# controlTP2.net
KiCad netlist of a schematic drawn in Altium Designer
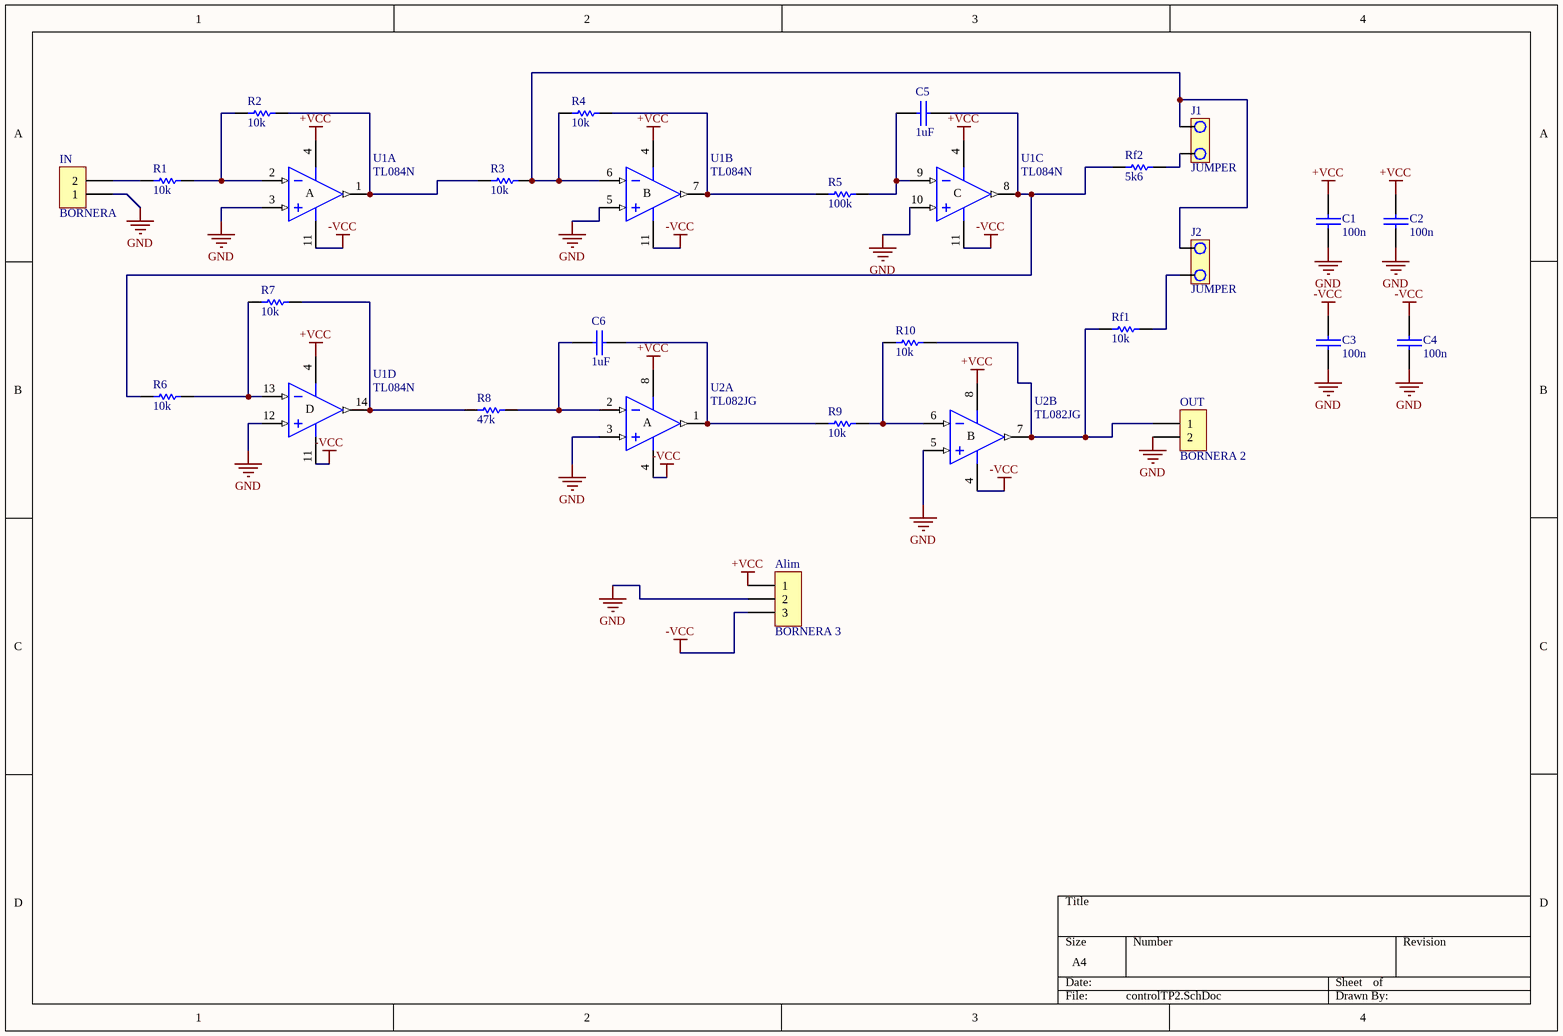
[diagram p0: controlTP2.SchDoc]

(export (version "E")
  (design (tool "Eeschema 10.0.6"))
  (components
    (comp (ref "Alim")
      (value "BORNERA 3")
      (footprint "BORNERA3")
      (libsource (lib "LIBEBAL") (part "BORNERA 3"))
    )
    (comp (ref "C1") (value "100n") (footprint "CAP200") (libsource (lib "LIBEBAL") (part "CAP")))
    (comp (ref "C2") (value "100n") (footprint "CAP200") (libsource (lib "LIBEBAL") (part "CAP")))
    (comp (ref "C3") (value "100n") (footprint "CAP200") (libsource (lib "LIBEBAL") (part "CAP")))
    (comp (ref "C4") (value "100n") (footprint "CAP200") (libsource (lib "LIBEBAL") (part "CAP")))
    (comp (ref "C5") (value "1uF") (footprint "CAP200") (libsource (lib "LIBEBAL") (part "CAP")))
    (comp (ref "C6") (value "1uF") (footprint "CAP200") (libsource (lib "LIBEBAL") (part "CAP")))
    (comp (ref "IN") (value "BORNERA") (footprint "BORNERA2") (libsource (lib "") (part "BORNERA 2_1")))
    (comp (ref "J1") (value "JUMPER") (footprint "JUMPER2") (libsource (lib "LIBEBAL") (part "JUMPER")))
    (comp (ref "J2") (value "JUMPER") (footprint "JUMPER2") (libsource (lib "LIBEBAL") (part "JUMPER")))
    (comp (ref "OUT")
      (value "BORNERA 2")
      (footprint "BORNERA2")
      (libsource (lib "LIBEBAL") (part "BORNERA 2"))
    )
    (comp (ref "R1") (value "10k") (footprint "RES400") (libsource (lib "LIBEBAL") (part "RES")))
    (comp (ref "R2") (value "10k") (footprint "RES400") (libsource (lib "LIBEBAL") (part "RES")))
    (comp (ref "R3") (value "10k") (footprint "RES400") (libsource (lib "LIBEBAL") (part "RES")))
    (comp (ref "R4") (value "10k") (footprint "RES400") (libsource (lib "LIBEBAL") (part "RES")))
    (comp (ref "R5") (value "100k") (footprint "RES400") (libsource (lib "LIBEBAL") (part "RES")))
    (comp (ref "R6") (value "10k") (footprint "RES400") (libsource (lib "LIBEBAL") (part "RES")))
    (comp (ref "R7") (value "10k") (footprint "RES400") (libsource (lib "LIBEBAL") (part "RES")))
    (comp (ref "R8") (value "47k") (footprint "RES400") (libsource (lib "LIBEBAL") (part "RES")))
    (comp (ref "R9") (value "10k") (footprint "RES400") (libsource (lib "LIBEBAL") (part "RES")))
    (comp (ref "R10") (value "10k") (footprint "RES400") (libsource (lib "LIBEBAL") (part "RES")))
    (comp (ref "Rf1") (value "10k") (footprint "RES400") (libsource (lib "LIBEBAL") (part "RES")))
    (comp (ref "Rf2") (value "5k6") (footprint "RES400") (libsource (lib "LIBEBAL") (part "RES")))
    (comp (ref "U1")
      (value "TL084N")
      (footprint "N014")
      (description "JFET-Input Operational Amplifier")
      (fields (field (name "PUBLISHER") "Altium Limited"))
      (libsource (lib "TI Operational Amplifier") (part "TL084N"))
    )
    (comp (ref "U2")
      (value "TL082JG")
      (footprint "JG008")
      (description "JFET-Input Operational Amplifier")
      (fields (field (name "PUBLISHER") "Altium Limited"))
      (libsource (lib "TI Operational Amplifier") (part "TL082JG"))
    )
  )
  (nets
    (net (code "1") (name "+VCC") (class "Default")
      (node (ref "Alim") (pin "1") (pinfunction "1_1") (pintype "passive"))
      (node (ref "C1") (pin "1") (pinfunction "1_1") (pintype "passive"))
      (node (ref "C2") (pin "1") (pinfunction "1_1") (pintype "passive"))
      (node (ref "U1") (pin "4") (pinfunction "V+_4") (pintype "power_in"))
      (node (ref "U2") (pin "8") (pinfunction "V+_8") (pintype "power_in"))
    )
    (net (code "2") (name "-VCC") (class "Default")
      (node (ref "Alim") (pin "3") (pinfunction "3_3") (pintype "passive"))
      (node (ref "C3") (pin "1") (pinfunction "1_1") (pintype "passive"))
      (node (ref "C4") (pin "1") (pinfunction "1_1") (pintype "passive"))
      (node (ref "U1") (pin "11") (pinfunction "V-_11") (pintype "power_in"))
      (node (ref "U2") (pin "4") (pinfunction "V-_4") (pintype "power_in"))
    )
    (net (code "3") (name "GND") (class "Default")
      (node (ref "Alim") (pin "2") (pinfunction "2_2") (pintype "passive"))
      (node (ref "C1") (pin "2") (pinfunction "2_2") (pintype "passive"))
      (node (ref "C2") (pin "2") (pinfunction "2_2") (pintype "passive"))
      (node (ref "C3") (pin "2") (pinfunction "2_2") (pintype "passive"))
      (node (ref "C4") (pin "2") (pinfunction "2_2") (pintype "passive"))
      (node (ref "IN") (pin "1") (pinfunction "1_1") (pintype "passive"))
      (node (ref "OUT") (pin "2") (pinfunction "2_2") (pintype "passive"))
      (node (ref "U1") (pin "10") (pinfunction "IN+_10") (pintype "input"))
      (node (ref "U1") (pin "12") (pinfunction "IN+_12") (pintype "input"))
      (node (ref "U1") (pin "3") (pinfunction "IN+_3") (pintype "input"))
      (node (ref "U1") (pin "5") (pinfunction "IN+_5") (pintype "input"))
      (node (ref "U2") (pin "3") (pinfunction "IN+_3") (pintype "input"))
      (node (ref "U2") (pin "5") (pinfunction "IN+_5") (pintype "input"))
    )
    (net (code "4") (name "Net-(IN-Pad2)") (class "Default")
      (node (ref "IN") (pin "2") (pinfunction "2_2") (pintype "passive"))
      (node (ref "R1") (pin "1") (pinfunction "1_1") (pintype "passive"))
    )
    (net (code "5") (name "Net-(J1-Pad1)") (class "Default")
      (node (ref "J1") (pin "1") (pinfunction "1_1") (pintype "passive"))
      (node (ref "Rf2") (pin "1") (pinfunction "1_1") (pintype "passive"))
    )
    (net (code "6") (name "Net-(J2-Pad1)") (class "Default")
      (node (ref "J2") (pin "1") (pinfunction "1_1") (pintype "passive"))
      (node (ref "Rf1") (pin "1") (pinfunction "1_1") (pintype "passive"))
    )
    (net (code "7") (name "Net-(U1A-IN-)") (class "Default")
      (node (ref "R1") (pin "2") (pinfunction "2_2") (pintype "passive"))
      (node (ref "R2") (pin "1") (pinfunction "1_1") (pintype "passive"))
      (node (ref "U1") (pin "2") (pinfunction "IN-_2") (pintype "input"))
    )
    (net (code "8") (name "Net-(U1A-OUT)") (class "Default")
      (node (ref "R2") (pin "2") (pinfunction "2_2") (pintype "passive"))
      (node (ref "R3") (pin "1") (pinfunction "1_1") (pintype "passive"))
      (node (ref "U1") (pin "1") (pinfunction "OUT_1") (pintype "output"))
    )
    (net (code "9") (name "Net-(U1B-IN-)") (class "Default")
      (node (ref "J1") (pin "2") (pinfunction "2_2") (pintype "passive"))
      (node (ref "J2") (pin "2") (pinfunction "2_2") (pintype "passive"))
      (node (ref "R3") (pin "2") (pinfunction "2_2") (pintype "passive"))
      (node (ref "R4") (pin "1") (pinfunction "1_1") (pintype "passive"))
      (node (ref "U1") (pin "6") (pinfunction "IN-_6") (pintype "input"))
    )
    (net (code "10") (name "Net-(U1B-OUT)") (class "Default")
      (node (ref "R4") (pin "2") (pinfunction "2_2") (pintype "passive"))
      (node (ref "R5") (pin "1") (pinfunction "1_1") (pintype "passive"))
      (node (ref "U1") (pin "7") (pinfunction "OUT_7") (pintype "output"))
    )
    (net (code "11") (name "Net-(U1C-IN-)") (class "Default")
      (node (ref "C5") (pin "1") (pinfunction "1_1") (pintype "passive"))
      (node (ref "R5") (pin "2") (pinfunction "2_2") (pintype "passive"))
      (node (ref "U1") (pin "9") (pinfunction "IN-_9") (pintype "input"))
    )
    (net (code "12") (name "Net-(U1C-OUT)") (class "Default")
      (node (ref "C5") (pin "2") (pinfunction "2_2") (pintype "passive"))
      (node (ref "R6") (pin "1") (pinfunction "1_1") (pintype "passive"))
      (node (ref "Rf2") (pin "2") (pinfunction "2_2") (pintype "passive"))
      (node (ref "U1") (pin "8") (pinfunction "OUT_8") (pintype "output"))
    )
    (net (code "13") (name "Net-(U1D-IN-)") (class "Default")
      (node (ref "R6") (pin "2") (pinfunction "2_2") (pintype "passive"))
      (node (ref "R7") (pin "1") (pinfunction "1_1") (pintype "passive"))
      (node (ref "U1") (pin "13") (pinfunction "IN-_13") (pintype "input"))
    )
    (net (code "14") (name "Net-(U1D-OUT)") (class "Default")
      (node (ref "R7") (pin "2") (pinfunction "2_2") (pintype "passive"))
      (node (ref "R8") (pin "1") (pinfunction "1_1") (pintype "passive"))
      (node (ref "U1") (pin "14") (pinfunction "OUT_14") (pintype "output"))
    )
    (net (code "15") (name "Net-(U2A-IN-)") (class "Default")
      (node (ref "C6") (pin "1") (pinfunction "1_1") (pintype "passive"))
      (node (ref "R8") (pin "2") (pinfunction "2_2") (pintype "passive"))
      (node (ref "U2") (pin "2") (pinfunction "IN-_2") (pintype "input"))
    )
    (net (code "16") (name "Net-(U2A-OUT)") (class "Default")
      (node (ref "C6") (pin "2") (pinfunction "2_2") (pintype "passive"))
      (node (ref "R9") (pin "1") (pinfunction "1_1") (pintype "passive"))
      (node (ref "U2") (pin "1") (pinfunction "OUT_1") (pintype "output"))
    )
    (net (code "17") (name "Net-(U2B-IN-)") (class "Default")
      (node (ref "R10") (pin "1") (pinfunction "1_1") (pintype "passive"))
      (node (ref "R9") (pin "2") (pinfunction "2_2") (pintype "passive"))
      (node (ref "U2") (pin "6") (pinfunction "IN-_6") (pintype "input"))
    )
    (net (code "18") (name "Net-(U2B-OUT)") (class "Default")
      (node (ref "OUT") (pin "1") (pinfunction "1_1") (pintype "passive"))
      (node (ref "R10") (pin "2") (pinfunction "2_2") (pintype "passive"))
      (node (ref "Rf1") (pin "2") (pinfunction "2_2") (pintype "passive"))
      (node (ref "U2") (pin "7") (pinfunction "OUT_7") (pintype "output"))
    )
  )
)
